# schematic.net
KiCad netlist of a schematic drawn in EasyEDA
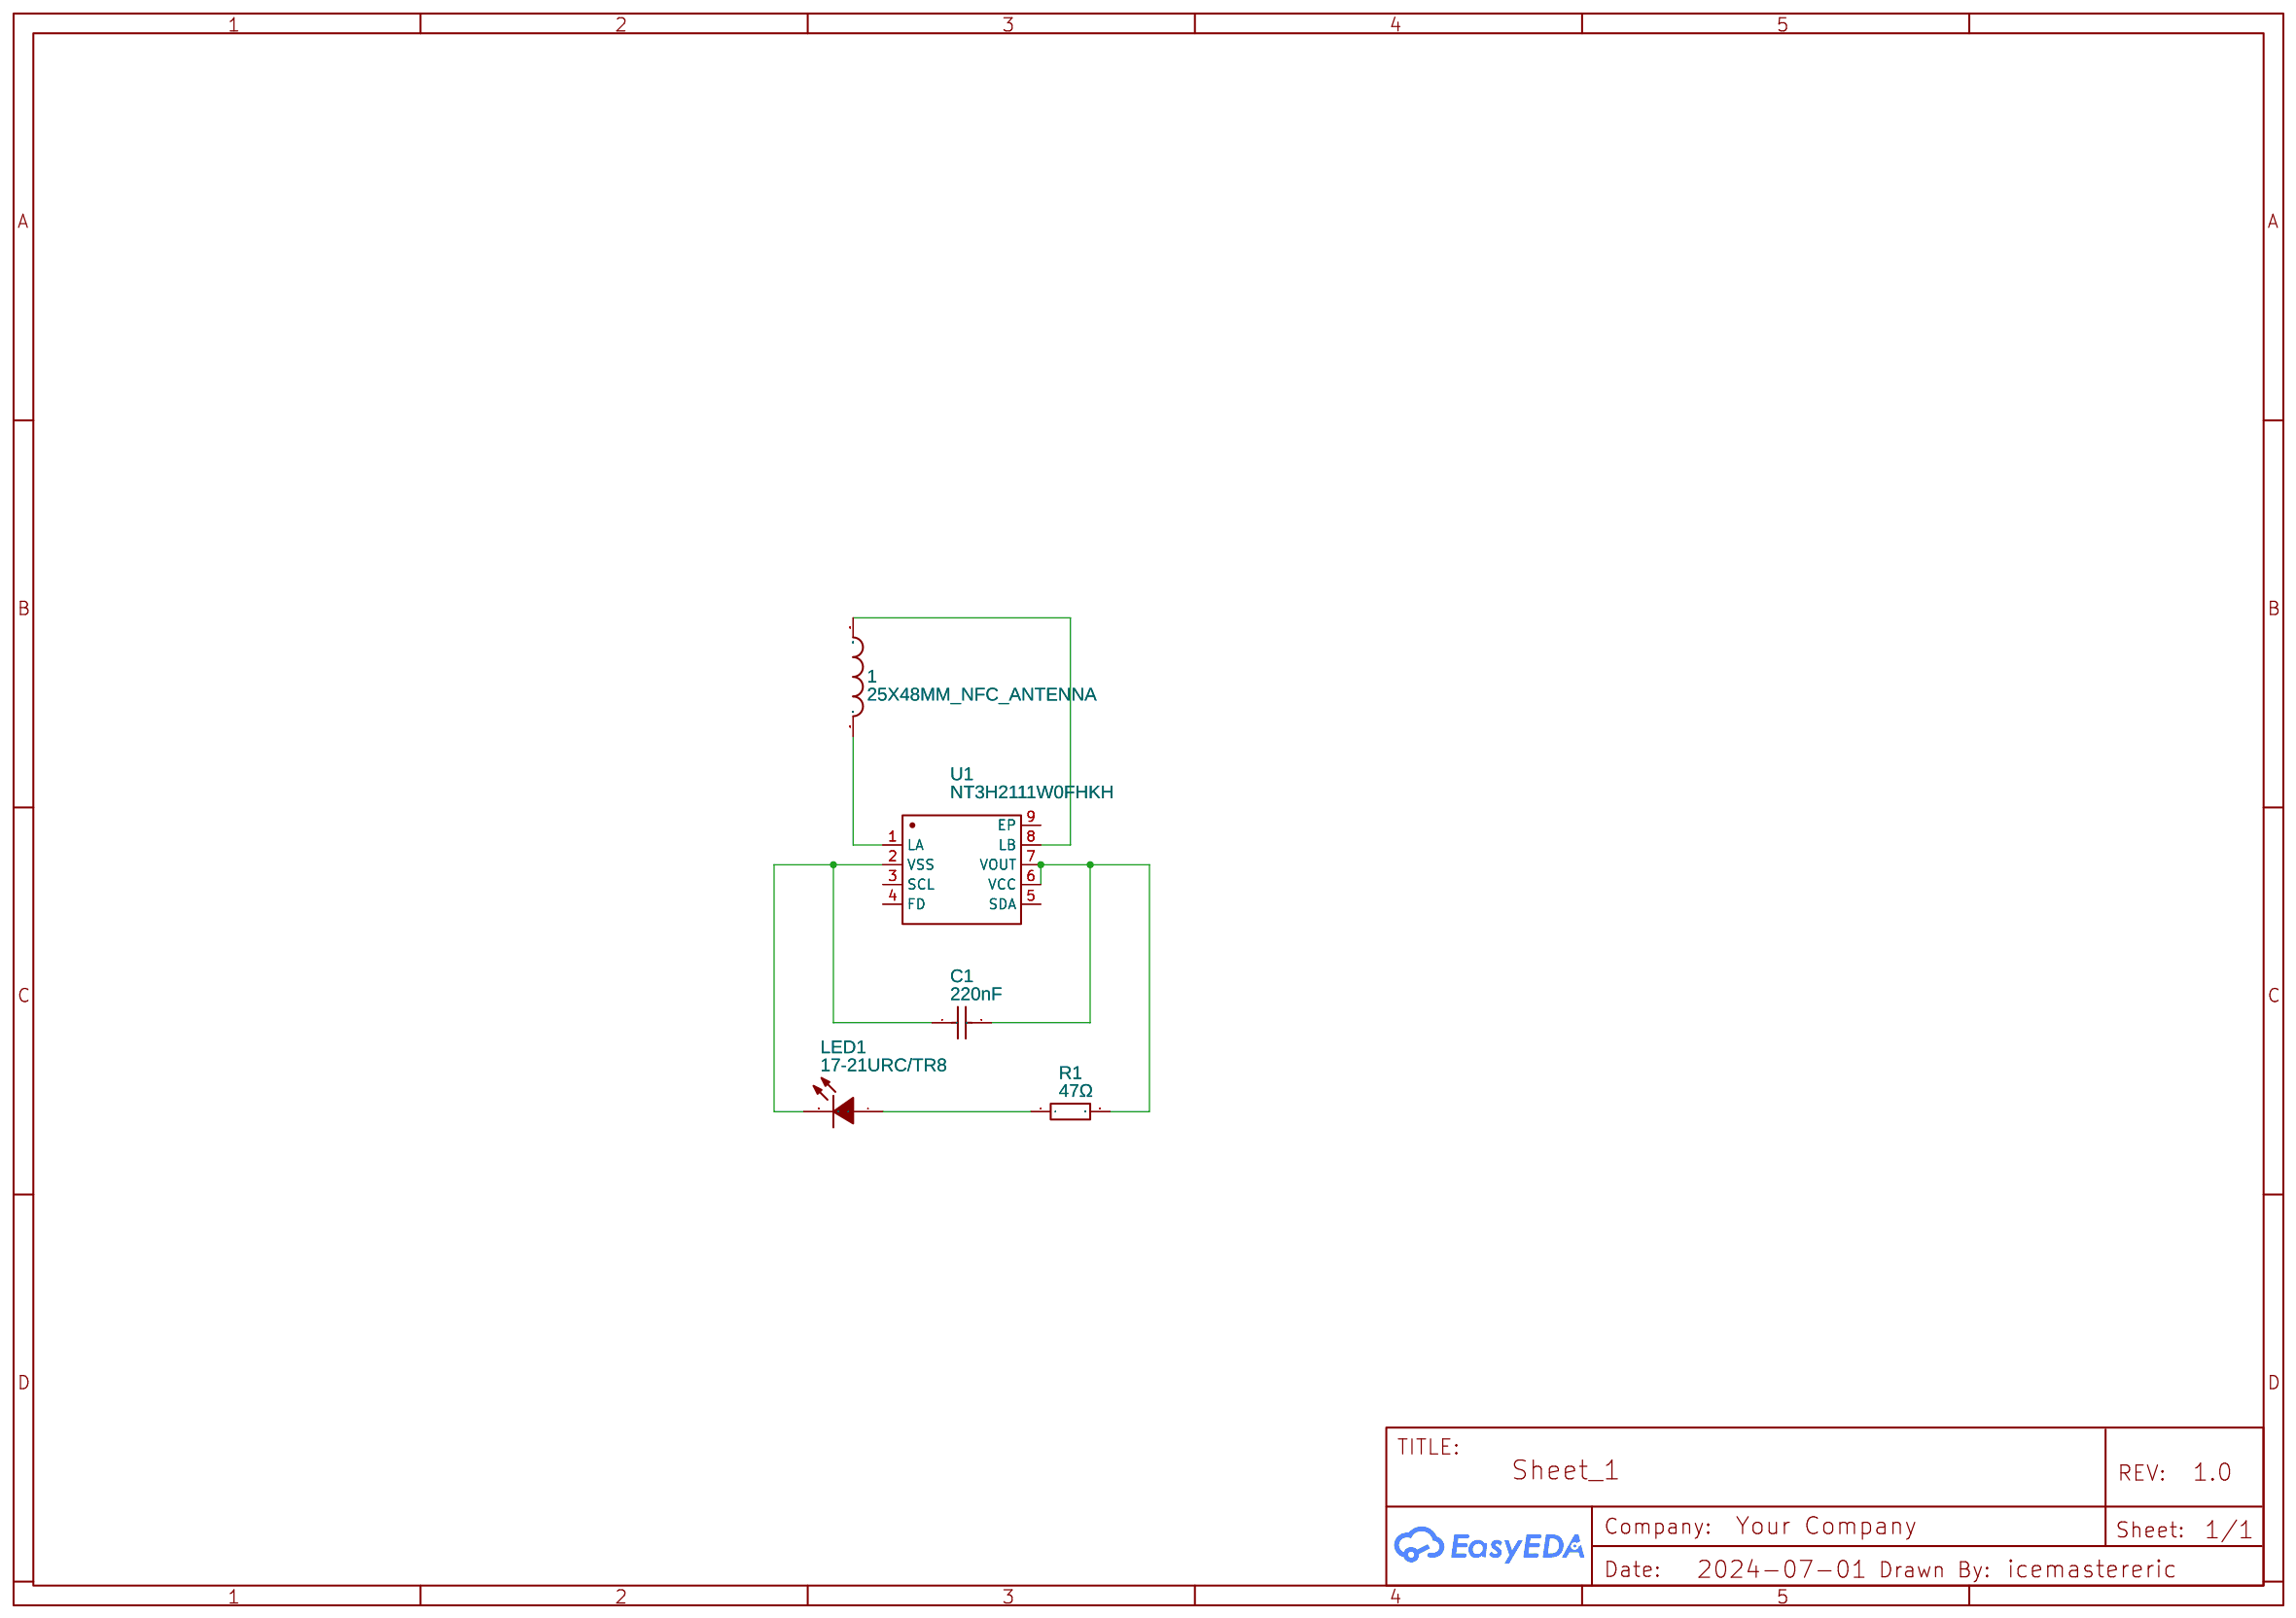
[diagram p0: schematic sheet]

(export (version "E")
  (design (tool "Eeschema 10.0.6"))
  (components
    (comp (ref "1") (value "25X48MM_NFC_ANTENNA") (libsource (lib "") (part "25X48MM_NFC_ANTENNA")))
    (comp (ref "C1")
      (value "220nF")
      (fields
        (field (name "Manufacturer Part") "CL10B224KA8NNNC")
        (field (name "Manufacturer") "SAMSUNG(三星)")
      )
      (libsource (lib "") (part "CL10B224KA8NNNC"))
    )
    (comp (ref "LED1")
      (value "17-21URC/TR8")
      (fields (field (name "Manufacturer") "EVERLIGHT(亿光)"))
      (libsource (lib "") (part "17-21URC/TR8"))
    )
    (comp (ref "R1")
      (value "47Ω")
      (fields
        (field (name "Manufacturer Part") "0603WAF470JT5E")
        (field (name "Manufacturer") "UNI-ROYAL(厚声)")
      )
      (libsource (lib "") (part "0603WAF470JT5E"))
    )
    (comp (ref "U1")
      (value "NT3H2111W0FHKH")
      (fields (field (name "Manufacturer") "NXP(恩智浦)"))
      (libsource (lib "") (part "NT3H2111W0FHKH"))
    )
  )
  (nets
    (net (code "1") (name "Net-(LED1-A)") (class "Default")
      (node (ref "LED1") (pin "1") (pinfunction "A_1") (pintype "unspecified"))
      (node (ref "R1") (pin "1") (pinfunction "1_1") (pintype "input"))
    )
    (net (code "2") (name "Net-(LED1-K)") (class "Default")
      (node (ref "C1") (pin "1") (pinfunction "1_1") (pintype "input"))
      (node (ref "LED1") (pin "2") (pinfunction "K_2") (pintype "unspecified"))
      (node (ref "U1") (pin "2") (pinfunction "VSS_2") (pintype "unspecified"))
    )
    (net (code "3") (name "Net-(U1-LA)") (class "Default")
      (node (ref "1") (pin "P$2") (pinfunction "P$2_P$2") (pintype "bidirectional"))
      (node (ref "U1") (pin "1") (pinfunction "LA_1") (pintype "unspecified"))
    )
    (net (code "4") (name "Net-(U1-LB)") (class "Default")
      (node (ref "1") (pin "P$1") (pinfunction "P$1_P$1") (pintype "bidirectional"))
      (node (ref "U1") (pin "8") (pinfunction "LB_8") (pintype "unspecified"))
    )
    (net (code "5") (name "Net-(U1-VCC)") (class "Default")
      (node (ref "C1") (pin "2") (pinfunction "2_2") (pintype "input"))
      (node (ref "R1") (pin "2") (pinfunction "2_2") (pintype "input"))
      (node (ref "U1") (pin "6") (pinfunction "VCC_6") (pintype "unspecified"))
      (node (ref "U1") (pin "7") (pinfunction "VOUT_7") (pintype "unspecified"))
    )
    (net (code "6") (name "unconnected-(U1-EP-Pad9)") (class "Default")
      (node (ref "U1") (pin "9") (pinfunction "EP_9") (pintype "unspecified"))
    )
    (net (code "7") (name "unconnected-(U1-FD-Pad4)") (class "Default")
      (node (ref "U1") (pin "4") (pinfunction "FD_4") (pintype "unspecified"))
    )
    (net (code "8") (name "unconnected-(U1-SCL-Pad3)") (class "Default")
      (node (ref "U1") (pin "3") (pinfunction "SCL_3") (pintype "unspecified"))
    )
    (net (code "9") (name "unconnected-(U1-SDA-Pad5)") (class "Default")
      (node (ref "U1") (pin "5") (pinfunction "SDA_5") (pintype "unspecified"))
    )
  )
)
